# Module-StepDown.net
KiCad netlist of a schematic drawn in EAGLE
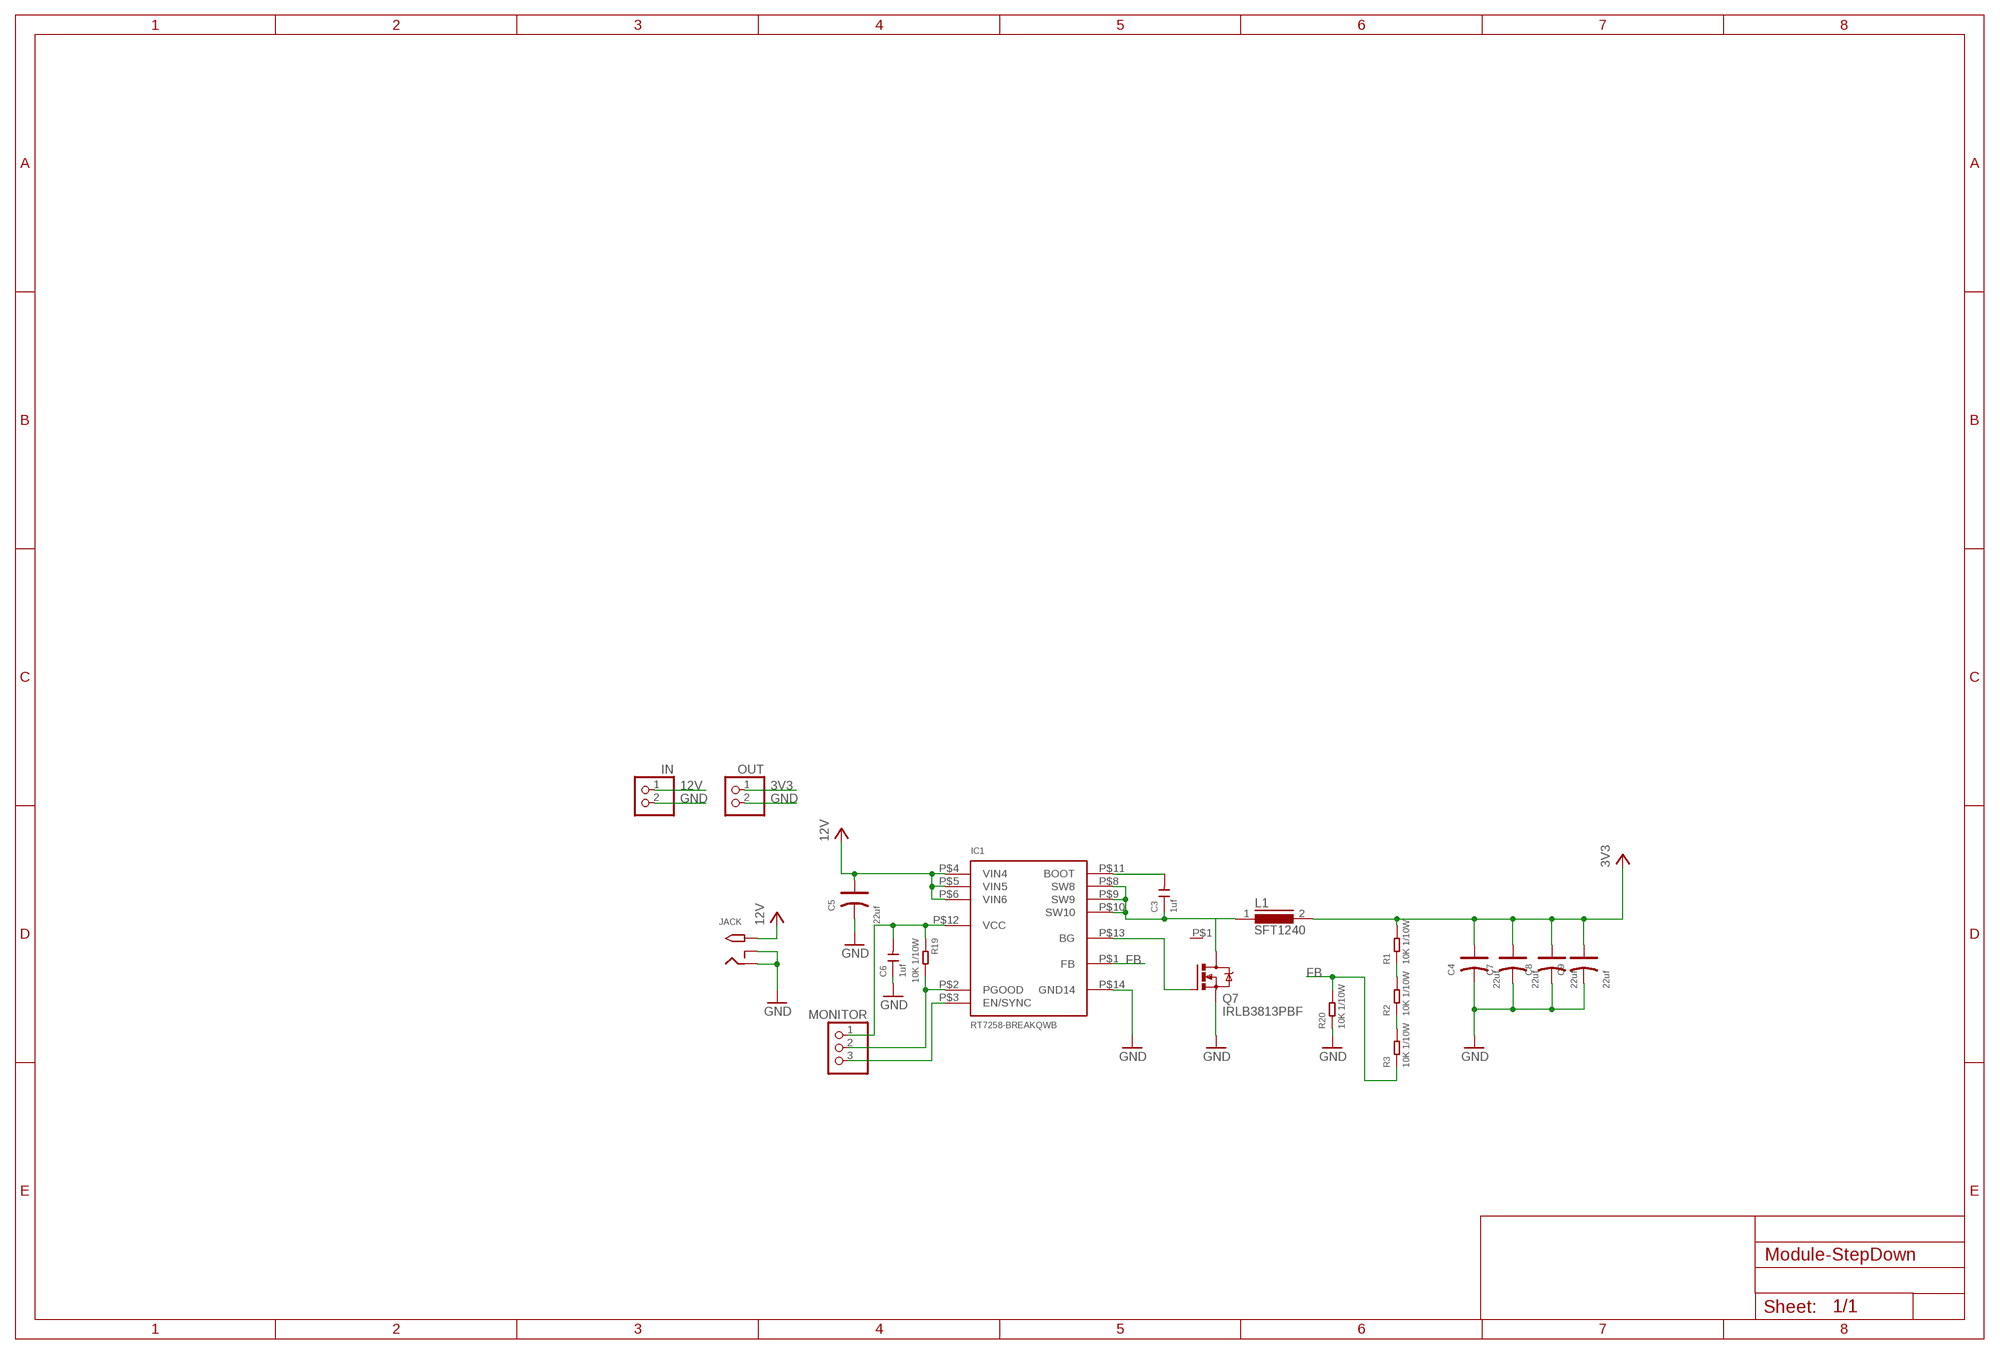
[diagram p0: schematic, sheet 1]

(export (version "E")
  (design (tool "Eeschema 10.0.6"))
  (components
    (comp (ref "C3")
      (value "1uf")
      (footprint "eagle-import:C0603")
      (fields (field (name "MPN") "CC0603KRX7R8BB105"))
      (libsource (lib "eagle-import") (part "CERAMIC-1UF-25V-10%-X7R(0603)"))
    )
    (comp (ref "C4")
      (value "22uf")
      (footprint "eagle-import:AVX-B")
      (fields (field (name "MPN") "TAJB226*016#NJ"))
      (libsource (lib "eagle-import") (part "TANTALUM-SMD-22UF-16V(AVX-B)"))
    )
    (comp (ref "C5")
      (value "22uf")
      (footprint "eagle-import:AVX-B")
      (fields (field (name "MPN") "TAJB226*016#NJ"))
      (libsource (lib "eagle-import") (part "TANTALUM-SMD-22UF-16V(AVX-B)"))
    )
    (comp (ref "C6")
      (value "1uf")
      (footprint "eagle-import:C0603")
      (fields (field (name "MPN") "CC0603KRX7R8BB105"))
      (libsource (lib "eagle-import") (part "CERAMIC-1UF-25V-10%-X7R(0603)"))
    )
    (comp (ref "C7")
      (value "22uf")
      (footprint "eagle-import:AVX-B")
      (fields (field (name "MPN") "TAJB226*016#NJ"))
      (libsource (lib "eagle-import") (part "TANTALUM-SMD-22UF-16V(AVX-B)"))
    )
    (comp (ref "C8")
      (value "22uf")
      (footprint "eagle-import:AVX-B")
      (fields (field (name "MPN") "TAJB226*016#NJ"))
      (libsource (lib "eagle-import") (part "TANTALUM-SMD-22UF-16V(AVX-B)"))
    )
    (comp (ref "C9")
      (value "22uf")
      (footprint "eagle-import:AVX-B")
      (fields (field (name "MPN") "TAJB226*016#NJ"))
      (libsource (lib "eagle-import") (part "TANTALUM-SMD-22UF-16V(AVX-B)"))
    )
    (comp (ref "HEATSINK1")
      (value "HEAT111PB015")
      (footprint "eagle-import:HEAT11PB015")
      (libsource (lib "eagle-import") (part "HEAT111PB015"))
    )
    (comp (ref "IC1")
      (value "RT7258-BREAKQWB")
      (footprint "eagle-import:RT7258GQW-BREAK")
      (libsource (lib "eagle-import") (part "RT7258-BREAKQWB"))
    )
    (comp (ref "IN")
      (value "PINHD-1X2")
      (footprint "eagle-import:1X02")
      (libsource (lib "eagle-import") (part "PINHD-1X2"))
    )
    (comp (ref "JACK")
      (value "2.1MMJACKTHM-NOOUT")
      (footprint "eagle-import:PJ-102A-NOOUT")
      (libsource (lib "eagle-import") (part "2.1MMJACKTHM-NOOUT"))
    )
    (comp (ref "L1")
      (value "SFT1240")
      (footprint "eagle-import:SFT1240")
      (libsource (lib "eagle-import") (part "SFT1240"))
    )
    (comp (ref "MONITOR")
      (value "PINHD-1X3")
      (footprint "eagle-import:1X03")
      (libsource (lib "eagle-import") (part "PINHD-1X3"))
    )
    (comp (ref "OUT")
      (value "PINHD-1X2")
      (footprint "eagle-import:1X02")
      (libsource (lib "eagle-import") (part "PINHD-1X2"))
    )
    (comp (ref "Q7")
      (value "IRLB3813PBF")
      (footprint "eagle-import:TO220BV")
      (libsource (lib "eagle-import") (part "IRF520"))
    )
    (comp (ref "R1")
      (value "10K 1/10W")
      (footprint "eagle-import:R0603")
      (fields (field (name "MPN") "RC0603JR-0710KL"))
      (libsource (lib "eagle-import") (part "SMD-RES-10K-5%-1/10W(0603)"))
    )
    (comp (ref "R2")
      (value "10K 1/10W")
      (footprint "eagle-import:R0603")
      (fields (field (name "MPN") "RC0603JR-0710KL"))
      (libsource (lib "eagle-import") (part "SMD-RES-10K-5%-1/10W(0603)"))
    )
    (comp (ref "R3")
      (value "10K 1/10W")
      (footprint "eagle-import:R0603")
      (fields (field (name "MPN") "RC0603JR-0710KL"))
      (libsource (lib "eagle-import") (part "SMD-RES-10K-5%-1/10W(0603)"))
    )
    (comp (ref "R19")
      (value "10K 1/10W")
      (footprint "eagle-import:R0603")
      (fields (field (name "MPN") "RC0603JR-0710KL"))
      (libsource (lib "eagle-import") (part "SMD-RES-10K-5%-1/10W(0603)"))
    )
    (comp (ref "R20")
      (value "10K 1/10W")
      (footprint "eagle-import:R0603")
      (fields (field (name "MPN") "RC0603JR-0710KL"))
      (libsource (lib "eagle-import") (part "SMD-RES-10K-5%-1/10W(0603)"))
    )
  )
  (nets
    (net (code "1") (name "/FB") (class "Default")
      (node (ref "IC1") (pin "P$1") (pinfunction "FB_P$1") (pintype "bidirectional"))
      (node (ref "R20") (pin "2") (pinfunction "2_2") (pintype "passive"))
      (node (ref "R3") (pin "1") (pinfunction "1_1") (pintype "passive"))
    )
    (net (code "2") (name "3V3") (class "Default")
      (node (ref "C4") (pin "+") (pinfunction "+_+") (pintype "passive"))
      (node (ref "C7") (pin "+") (pinfunction "+_+") (pintype "passive"))
      (node (ref "C8") (pin "+") (pinfunction "+_+") (pintype "passive"))
      (node (ref "C9") (pin "+") (pinfunction "+_+") (pintype "passive"))
      (node (ref "L1") (pin "2") (pinfunction "2_2") (pintype "passive"))
      (node (ref "OUT") (pin "1") (pinfunction "1_1") (pintype "passive"))
      (node (ref "R1") (pin "2") (pinfunction "2_2") (pintype "passive"))
    )
    (net (code "3") (name "12V") (class "Default")
      (node (ref "C5") (pin "+") (pinfunction "+_+") (pintype "passive"))
      (node (ref "IC1") (pin "P$4") (pinfunction "VIN4_P$4") (pintype "bidirectional"))
      (node (ref "IC1") (pin "P$5") (pinfunction "VIN5_P$5") (pintype "bidirectional"))
      (node (ref "IC1") (pin "P$6") (pinfunction "VIN6_P$6") (pintype "bidirectional"))
      (node (ref "IN") (pin "1") (pinfunction "1_1") (pintype "passive"))
      (node (ref "JACK") (pin "TIP") (pinfunction "TIP_TIP") (pintype "bidirectional"))
    )
    (net (code "4") (name "GND") (class "Default")
      (node (ref "C4") (pin "-") (pinfunction "-_-") (pintype "passive"))
      (node (ref "C5") (pin "-") (pinfunction "-_-") (pintype "passive"))
      (node (ref "C6") (pin "1") (pinfunction "1_1") (pintype "passive"))
      (node (ref "C7") (pin "-") (pinfunction "-_-") (pintype "passive"))
      (node (ref "C8") (pin "-") (pinfunction "-_-") (pintype "passive"))
      (node (ref "C9") (pin "-") (pinfunction "-_-") (pintype "passive"))
      (node (ref "IC1") (pin "P$14") (pinfunction "GND14_P$14") (pintype "bidirectional"))
      (node (ref "IN") (pin "2") (pinfunction "2_2") (pintype "passive"))
      (node (ref "JACK") (pin "RING") (pinfunction "RING_RING") (pintype "bidirectional"))
      (node (ref "JACK") (pin "RING_SW") (pinfunction "RING_SW_RING_SW") (pintype "bidirectional"))
      (node (ref "OUT") (pin "2") (pinfunction "2_2") (pintype "passive"))
      (node (ref "Q7") (pin "S") (pinfunction "S_S") (pintype "passive"))
      (node (ref "R20") (pin "1") (pinfunction "1_1") (pintype "passive"))
    )
    (net (code "5") (name "Net-(IC1-BG)") (class "Default")
      (node (ref "IC1") (pin "P$13") (pinfunction "BG_P$13") (pintype "bidirectional"))
      (node (ref "Q7") (pin "G") (pinfunction "G_G") (pintype "passive"))
    )
    (net (code "6") (name "Net-(IC1-BOOT)") (class "Default")
      (node (ref "C3") (pin "2") (pinfunction "2_2") (pintype "passive"))
      (node (ref "IC1") (pin "P$11") (pinfunction "BOOT_P$11") (pintype "bidirectional"))
    )
    (net (code "7") (name "Net-(IC1-EN{slash}SYNC)") (class "Default")
      (node (ref "IC1") (pin "P$3") (pinfunction "EN/SYNC_P$3") (pintype "bidirectional"))
      (node (ref "MONITOR") (pin "3") (pinfunction "3_3") (pintype "passive"))
    )
    (net (code "8") (name "Net-(IC1-PGOOD)") (class "Default")
      (node (ref "IC1") (pin "P$2") (pinfunction "PGOOD_P$2") (pintype "bidirectional"))
      (node (ref "MONITOR") (pin "2") (pinfunction "2_2") (pintype "passive"))
      (node (ref "R19") (pin "2") (pinfunction "2_2") (pintype "passive"))
    )
    (net (code "9") (name "Net-(IC1-SW10)") (class "Default")
      (node (ref "C3") (pin "1") (pinfunction "1_1") (pintype "passive"))
      (node (ref "IC1") (pin "P$10") (pinfunction "SW10_P$10") (pintype "bidirectional"))
      (node (ref "IC1") (pin "P$8") (pinfunction "SW8_P$8") (pintype "bidirectional"))
      (node (ref "IC1") (pin "P$9") (pinfunction "SW9_P$9") (pintype "bidirectional"))
      (node (ref "L1") (pin "1") (pinfunction "1_1") (pintype "passive"))
      (node (ref "Q7") (pin "D") (pinfunction "D_D") (pintype "passive"))
    )
    (net (code "10") (name "Net-(IC1-VCC)") (class "Default")
      (node (ref "C6") (pin "2") (pinfunction "2_2") (pintype "passive"))
      (node (ref "IC1") (pin "P$12") (pinfunction "VCC_P$12") (pintype "bidirectional"))
      (node (ref "MONITOR") (pin "1") (pinfunction "1_1") (pintype "passive"))
      (node (ref "R19") (pin "1") (pinfunction "1_1") (pintype "passive"))
    )
    (net (code "11") (name "Net-(R1-Pad1)") (class "Default")
      (node (ref "R1") (pin "1") (pinfunction "1_1") (pintype "passive"))
      (node (ref "R2") (pin "2") (pinfunction "2_2") (pintype "passive"))
    )
    (net (code "12") (name "Net-(R2-Pad1)") (class "Default")
      (node (ref "R2") (pin "1") (pinfunction "1_1") (pintype "passive"))
      (node (ref "R3") (pin "2") (pinfunction "2_2") (pintype "passive"))
    )
    (net (code "13") (name "unconnected-(HEATSINK1-PadP$1)") (class "Default")
      (node (ref "HEATSINK1") (pin "P$1") (pinfunction "P$1_P$1") (pintype "bidirectional"))
    )
  )
)
